# Commuta_PCBv2.net
KiCad netlist of a schematic drawn in EasyEDA Pro
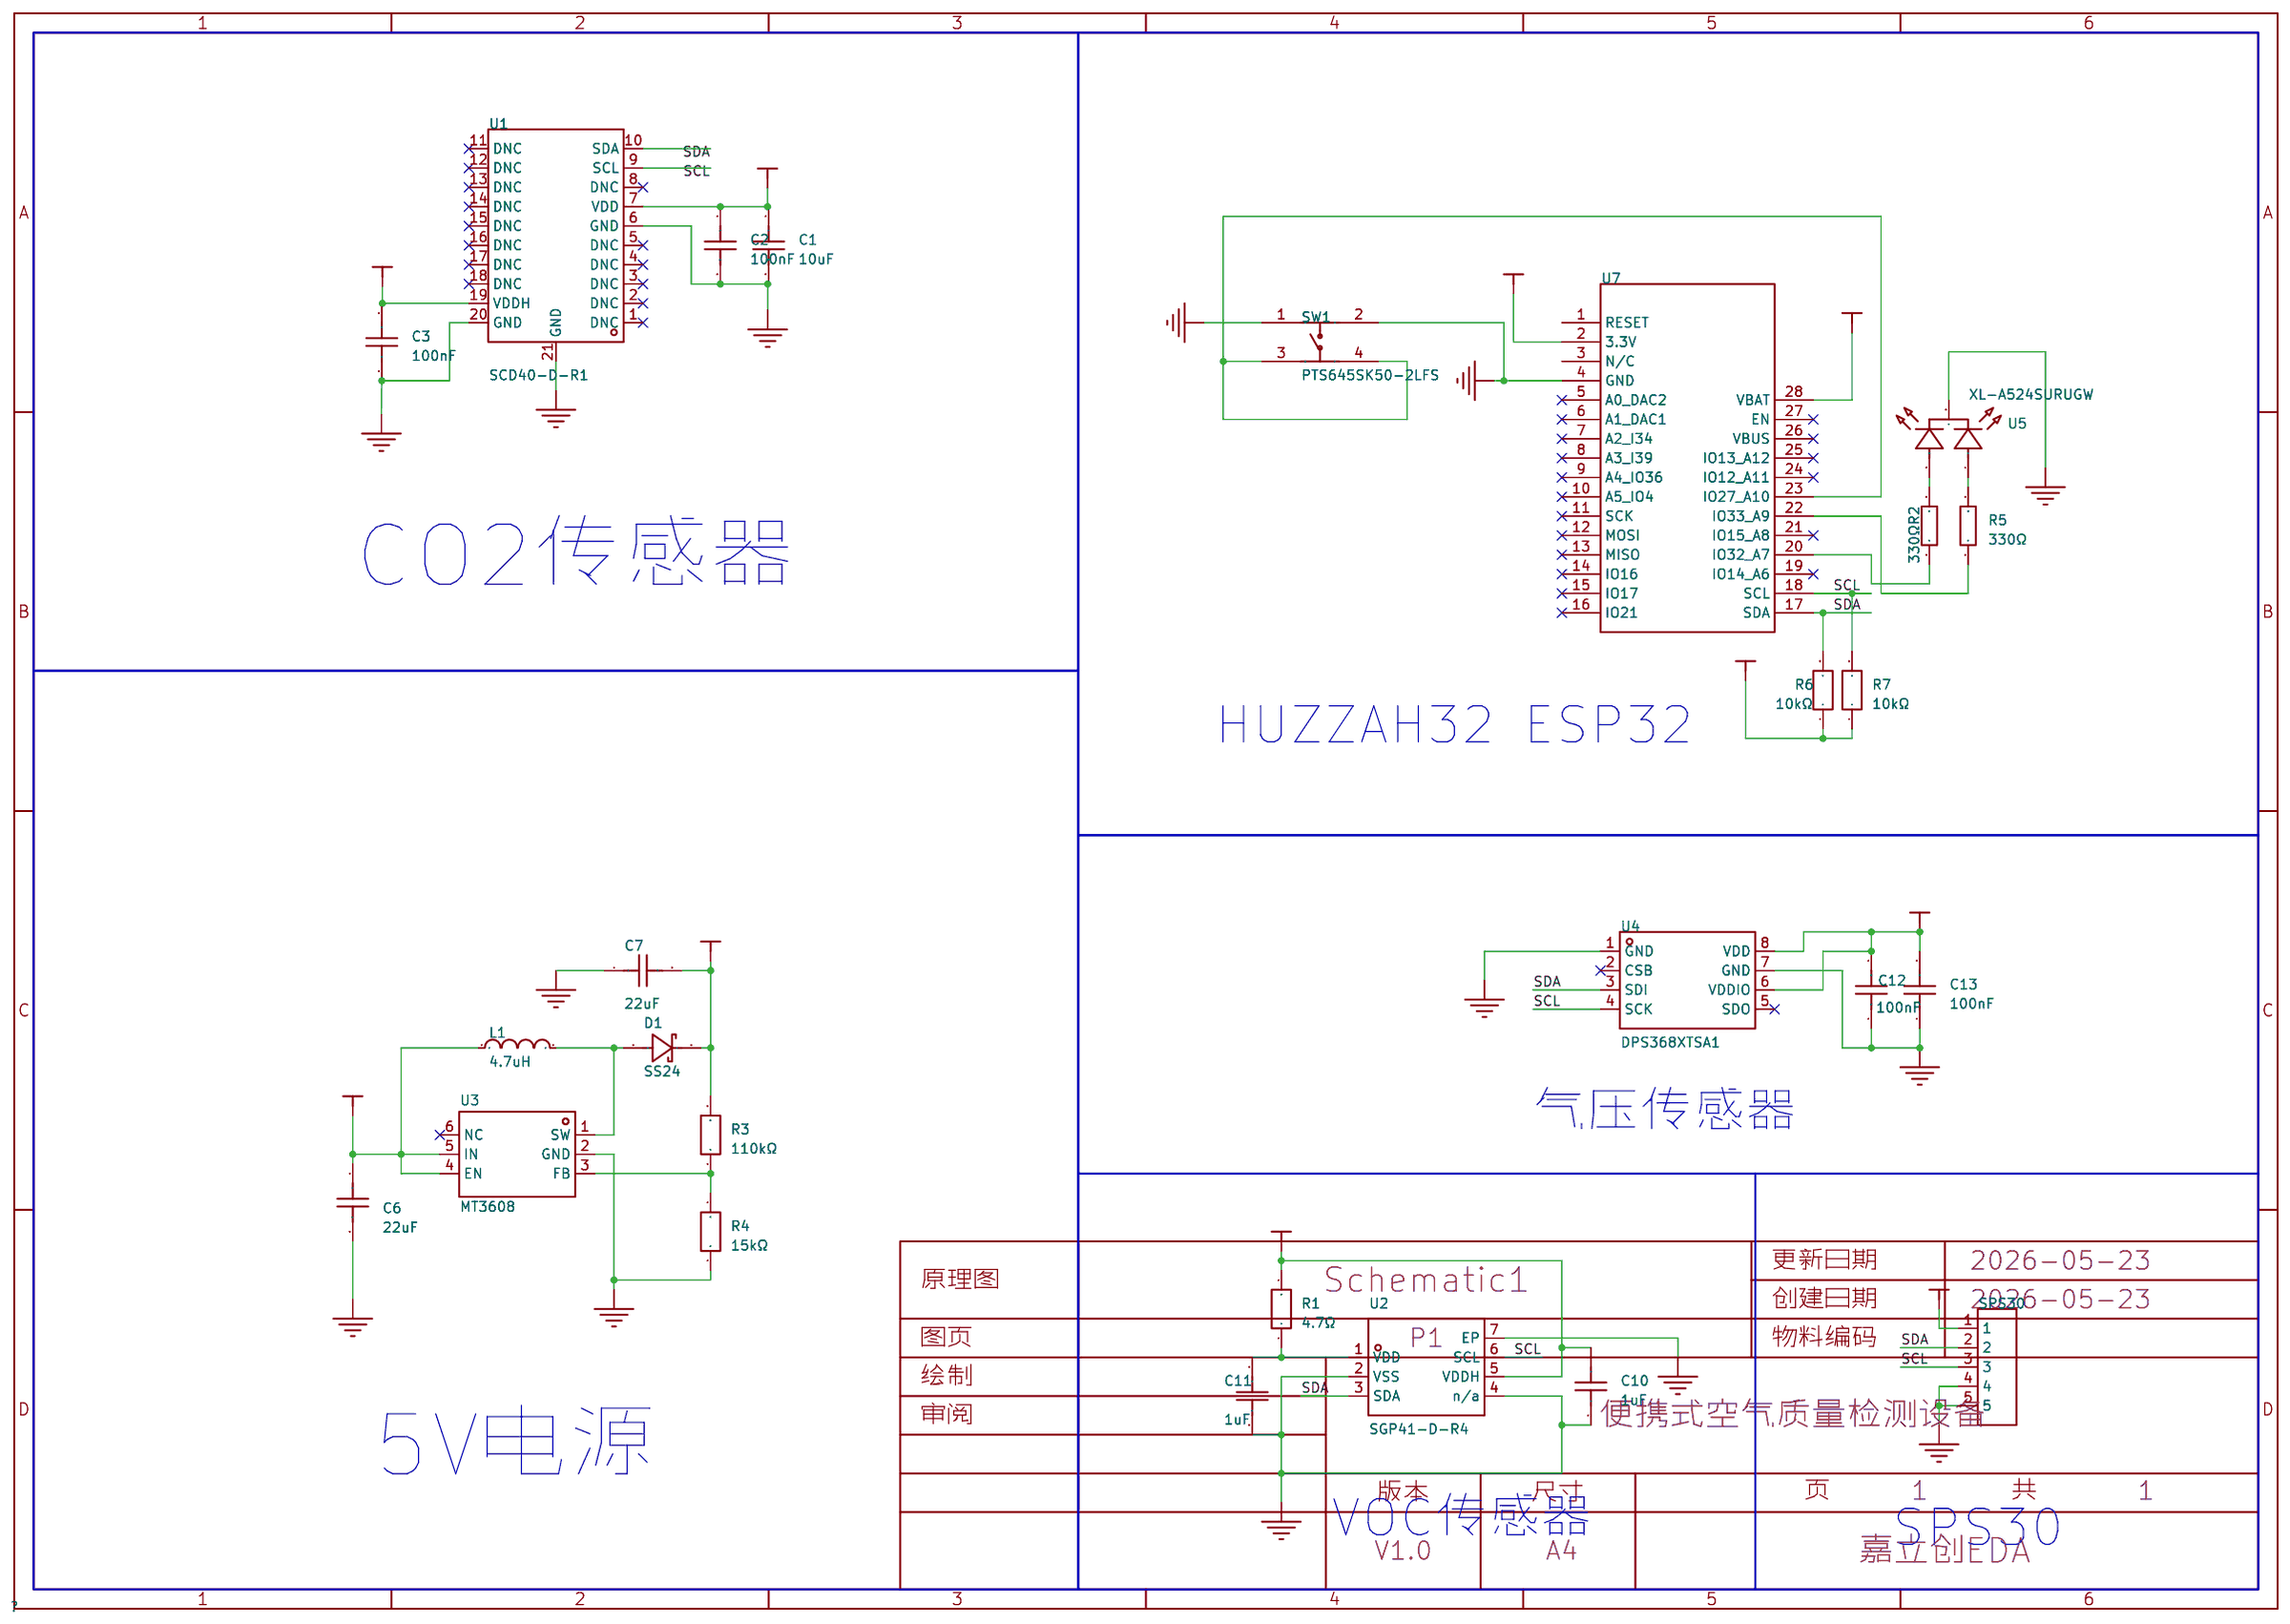
[diagram p0: schematic sheet]

(export (version "E")
  (design (tool "Eeschema 10.0.6"))
  (components
    (comp (ref "C1")
      (value "10uF")
      (footprint "easyedapro:C0805")
      (fields
        (field (name "Manufacturer Part") "CGA0805X5R106K250MT")
        (field (name "Manufacturer") "HRE(芯声)")
      )
      (libsource (lib "easyedapro") (part "CGA0805X5R106K250MT"))
    )
    (comp (ref "C2")
      (value "100nF")
      (footprint "easyedapro:C0603")
      (fields
        (field (name "Manufacturer Part") "CGA0603X7R104K500JT")
        (field (name "Manufacturer") "HRE(芯声)")
      )
      (libsource (lib "easyedapro") (part "CGA0603X7R104K500JT"))
    )
    (comp (ref "C3")
      (value "100nF")
      (footprint "easyedapro:C0603")
      (fields
        (field (name "Manufacturer Part") "CGA0603X7R104K500JT")
        (field (name "Manufacturer") "HRE(芯声)")
      )
      (libsource (lib "easyedapro") (part "CGA0603X7R104K500JT"))
    )
    (comp (ref "C6")
      (value "22uF")
      (footprint "easyedapro:C0603")
      (fields
        (field (name "Manufacturer Part") "CGA0603X5R226M160JT")
        (field (name "Manufacturer") "HRE(芯声)")
      )
      (libsource (lib "easyedapro") (part "CGA0603X5R226M160JT"))
    )
    (comp (ref "C7")
      (value "22uF")
      (footprint "easyedapro:C0603")
      (fields
        (field (name "Manufacturer Part") "CGA0603X5R226M160JT")
        (field (name "Manufacturer") "HRE(芯声)")
      )
      (libsource (lib "easyedapro") (part "CGA0603X5R226M160JT"))
    )
    (comp (ref "C10")
      (value "1uF")
      (footprint "easyedapro:C0603")
      (fields
        (field (name "Manufacturer Part") "CGA0603X5R105K500JT")
        (field (name "Manufacturer") "HRE(芯声)")
      )
      (libsource (lib "easyedapro") (part "CGA0603X5R105K500JT"))
    )
    (comp (ref "C11")
      (value "1uF")
      (footprint "easyedapro:C0603")
      (fields
        (field (name "Manufacturer Part") "CGA0603X5R105K500JT")
        (field (name "Manufacturer") "HRE(芯声)")
      )
      (libsource (lib "easyedapro") (part "CGA0603X5R105K500JT"))
    )
    (comp (ref "C12")
      (value "100nF")
      (footprint "easyedapro:C0603")
      (fields
        (field (name "Manufacturer Part") "CGA0603X7R104K500JT")
        (field (name "Manufacturer") "HRE(芯声)")
      )
      (libsource (lib "easyedapro") (part "CGA0603X7R104K500JT"))
    )
    (comp (ref "C13")
      (value "100nF")
      (footprint "easyedapro:C0603")
      (fields
        (field (name "Manufacturer Part") "CGA0603X7R104K500JT")
        (field (name "Manufacturer") "HRE(芯声)")
      )
      (libsource (lib "easyedapro") (part "CGA0603X7R104K500JT"))
    )
    (comp (ref "D1")
      (value "SS24")
      (footprint "easyedapro:SMA_L4.3-W2.6-LS5.0-FD")
      (fields (field (name "Manufacturer") "R+O(宏嘉诚)"))
      (libsource (lib "easyedapro") (part "SS24_C7420362"))
    )
    (comp (ref "L1")
      (value "4.7uH")
      (footprint "easyedapro:IND-SMD_L5.0-W5.0_FNR50XXS")
      (fields (field (name "Manufacturer Part") "FNR5040S4R7MT") (field (name "Manufacturer") "cjiang(长江微电)"))
      (libsource (lib "easyedapro") (part "FNR5040S4R7MT"))
    )
    (comp (ref "R1")
      (value "4.7Ω")
      (footprint "easyedapro:R0603")
      (fields (field (name "Manufacturer Part") "FRC0603F1001TS") (field (name "Manufacturer") "FOJAN(富捷)"))
      (libsource (lib "easyedapro") (part "FRC0603F1001TS"))
    )
    (comp (ref "R2")
      (value "330Ω")
      (footprint "easyedapro:R0603")
      (fields
        (field (name "Manufacturer Part") "0603WAF3303T5E")
        (field (name "Manufacturer") "UNI-ROYAL(厚声)")
      )
      (libsource (lib "easyedapro") (part "0603WAF3303T5E"))
    )
    (comp (ref "R3")
      (value "110kΩ")
      (footprint "easyedapro:R0603")
      (fields (field (name "Manufacturer Part") "FRC0603F1103TS") (field (name "Manufacturer") "FOJAN(富捷)"))
      (libsource (lib "easyedapro") (part "FRC0603F1103TS"))
    )
    (comp (ref "R4")
      (value "15kΩ")
      (footprint "easyedapro:R0603")
      (fields (field (name "Manufacturer Part") "FRC0603F1502TS") (field (name "Manufacturer") "FOJAN(富捷)"))
      (libsource (lib "easyedapro") (part "FRC0603F1502TS"))
    )
    (comp (ref "R5")
      (value "330Ω")
      (footprint "easyedapro:R0603")
      (fields
        (field (name "Manufacturer Part") "0603WAF3303T5E")
        (field (name "Manufacturer") "UNI-ROYAL(厚声)")
      )
      (libsource (lib "easyedapro") (part "0603WAF3303T5E"))
    )
    (comp (ref "R6")
      (value "10kΩ")
      (footprint "easyedapro:R0603")
      (fields (field (name "Manufacturer Part") "FRC0603J103 TS") (field (name "Manufacturer") "FOJAN(富捷)"))
      (libsource (lib "easyedapro") (part "FRC0603J103TS"))
    )
    (comp (ref "R7")
      (value "10kΩ")
      (footprint "easyedapro:R0603")
      (fields (field (name "Manufacturer Part") "FRC0603J103 TS") (field (name "Manufacturer") "FOJAN(富捷)"))
      (libsource (lib "easyedapro") (part "FRC0603J103TS"))
    )
    (comp (ref "SPS30")
      (value "PZ254V-11-05P")
      (footprint "easyedapro:HDR-TH_5P-P2.54-V-M")
      (fields (field (name "Manufacturer") "XFCN(兴飞)"))
      (libsource (lib "easyedapro") (part "PZ254V-11-05P"))
    )
    (comp (ref "SW1")
      (value "PTS645SK50-2LFS")
      (footprint "easyedapro:KEY-TH_4P-L6.0-W6.0-P4.50-LS6.50")
      (fields (field (name "Manufacturer") "C&K"))
      (libsource (lib "easyedapro") (part "PTS645SK50-2LFS"))
    )
    (comp (ref "U1")
      (value "SCD40-D-R1")
      (footprint "easyedapro:LGA-20_L10.1-W10.1-P1.25-TL")
      (fields (field (name "Manufacturer") "Sensirion(瑞士盛思锐)"))
      (libsource (lib "easyedapro") (part "SCD40-D-R1"))
    )
    (comp (ref "U2")
      (value "SGP41-D-R4")
      (footprint "easyedapro:DFN-6_L2.4-W2.4-P0.80-TL-EP")
      (fields (field (name "Manufacturer") "Sensirion(瑞士盛思锐)"))
      (libsource (lib "easyedapro") (part "SGP41-D-R4"))
    )
    (comp (ref "U3")
      (value "MT3608")
      (footprint "easyedapro:SOT-23-6_L2.9-W1.6-P0.95-LS2.8-BL")
      (fields (field (name "Manufacturer") "西安航天民芯"))
      (libsource (lib "easyedapro") (part "MT3608"))
    )
    (comp (ref "U4")
      (value "DPS368XTSA1")
      (footprint "easyedapro:LGA-8_L2.5-W2.0-P0.65-TR_DPS368")
      (fields (field (name "Manufacturer") "Infineon(英飞凌)"))
      (libsource (lib "easyedapro") (part "DPS368XTSA1"))
    )
    (comp (ref "U5")
      (value "XL-A524SURUGW")
      (footprint "easyedapro:LED-TH_3P-BD5.8-P2.54-1")
      (fields (field (name "Manufacturer") "XINGLIGHT(成兴光)"))
      (libsource (lib "easyedapro") (part "XL-A524SURUGW"))
    )
    (comp (ref "U7") (value "~") (libsource (lib "easyedapro") (part "HUZZAH32 ESP32")))
  )
  (nets
    (net (code "1") (name "+3.3V") (class "Default")
      (node (ref "C1") (pin "1") (pinfunction "1_1") (pintype "unspecified"))
      (node (ref "C10") (pin "2") (pinfunction "2_2") (pintype "unspecified"))
      (node (ref "C12") (pin "2") (pinfunction "2_2") (pintype "unspecified"))
      (node (ref "C13") (pin "2") (pinfunction "2_2") (pintype "unspecified"))
      (node (ref "C2") (pin "1") (pinfunction "1_1") (pintype "unspecified"))
      (node (ref "C3") (pin "1") (pinfunction "1_1") (pintype "unspecified"))
      (node (ref "R1") (pin "2") (pinfunction "2_2") (pintype "unspecified"))
      (node (ref "R6") (pin "1") (pinfunction "1_1") (pintype "unspecified"))
      (node (ref "R7") (pin "1") (pinfunction "1_1") (pintype "unspecified"))
      (node (ref "U1") (pin "19") (pinfunction "VDDH_19") (pintype "unspecified"))
      (node (ref "U1") (pin "7") (pinfunction "VDD_7") (pintype "unspecified"))
      (node (ref "U2") (pin "5") (pinfunction "VDDH_5") (pintype "unspecified"))
      (node (ref "U4") (pin "6") (pinfunction "VDDIO_6") (pintype "unspecified"))
      (node (ref "U4") (pin "8") (pinfunction "VDD_8") (pintype "unspecified"))
      (node (ref "U7") (pin "2") (pinfunction "3.3V_2") (pintype "unspecified"))
    )
    (net (code "2") (name "+5V") (class "Default")
      (node (ref "C7") (pin "2") (pinfunction "2_2") (pintype "unspecified"))
      (node (ref "D1") (pin "2") (pinfunction "K_2") (pintype "unspecified"))
      (node (ref "R3") (pin "2") (pinfunction "2_2") (pintype "unspecified"))
      (node (ref "SPS30") (pin "1") (pinfunction "1_1") (pintype "unspecified"))
    )
    (net (code "3") (name "/SCL") (class "Default")
      (node (ref "R7") (pin "2") (pinfunction "2_2") (pintype "unspecified"))
      (node (ref "SPS30") (pin "3") (pinfunction "3_3") (pintype "unspecified"))
      (node (ref "U1") (pin "9") (pinfunction "SCL_9") (pintype "unspecified"))
      (node (ref "U2") (pin "6") (pinfunction "SCL_6") (pintype "unspecified"))
      (node (ref "U4") (pin "4") (pinfunction "SCK_4") (pintype "unspecified"))
      (node (ref "U7") (pin "18") (pinfunction "SCL_18") (pintype "unspecified"))
    )
    (net (code "4") (name "/SDA") (class "Default")
      (node (ref "R6") (pin "2") (pinfunction "2_2") (pintype "unspecified"))
      (node (ref "SPS30") (pin "2") (pinfunction "2_2") (pintype "unspecified"))
      (node (ref "U1") (pin "10") (pinfunction "SDA_10") (pintype "unspecified"))
      (node (ref "U2") (pin "3") (pinfunction "SDA_3") (pintype "unspecified"))
      (node (ref "U4") (pin "3") (pinfunction "SDI_3") (pintype "unspecified"))
      (node (ref "U7") (pin "17") (pinfunction "SDA_17") (pintype "unspecified"))
    )
    (net (code "5") (name "GND") (class "Default")
      (node (ref "C1") (pin "2") (pinfunction "2_2") (pintype "unspecified"))
      (node (ref "C10") (pin "1") (pinfunction "1_1") (pintype "unspecified"))
      (node (ref "C11") (pin "2") (pinfunction "2_2") (pintype "unspecified"))
      (node (ref "C12") (pin "1") (pinfunction "1_1") (pintype "unspecified"))
      (node (ref "C13") (pin "1") (pinfunction "1_1") (pintype "unspecified"))
      (node (ref "C2") (pin "2") (pinfunction "2_2") (pintype "unspecified"))
      (node (ref "C3") (pin "2") (pinfunction "2_2") (pintype "unspecified"))
      (node (ref "C6") (pin "2") (pinfunction "2_2") (pintype "unspecified"))
      (node (ref "C7") (pin "1") (pinfunction "1_1") (pintype "unspecified"))
      (node (ref "R4") (pin "1") (pinfunction "1_1") (pintype "unspecified"))
      (node (ref "SPS30") (pin "4") (pinfunction "4_4") (pintype "unspecified"))
      (node (ref "SPS30") (pin "5") (pinfunction "5_5") (pintype "unspecified"))
      (node (ref "SW1") (pin "1") (pinfunction "1_1") (pintype "unspecified"))
      (node (ref "SW1") (pin "2") (pinfunction "2_2") (pintype "unspecified"))
      (node (ref "U1") (pin "20") (pinfunction "GND_20") (pintype "unspecified"))
      (node (ref "U1") (pin "21") (pinfunction "GND_21") (pintype "unspecified"))
      (node (ref "U1") (pin "6") (pinfunction "GND_6") (pintype "unspecified"))
      (node (ref "U2") (pin "2") (pinfunction "VSS_2") (pintype "unspecified"))
      (node (ref "U2") (pin "4") (pinfunction "n/a_4") (pintype "unspecified"))
      (node (ref "U2") (pin "7") (pinfunction "EP_7") (pintype "unspecified"))
      (node (ref "U3") (pin "2") (pinfunction "GND_2") (pintype "unspecified"))
      (node (ref "U4") (pin "1") (pinfunction "GND_1") (pintype "unspecified"))
      (node (ref "U4") (pin "7") (pinfunction "GND_7") (pintype "unspecified"))
      (node (ref "U5") (pin "2") (pinfunction "K_2") (pintype "unspecified"))
      (node (ref "U7") (pin "4") (pinfunction "GND_4") (pintype "unspecified"))
    )
    (net (code "6") (name "Net-(D1-A)") (class "Default")
      (node (ref "D1") (pin "1") (pinfunction "A_1") (pintype "unspecified"))
      (node (ref "L1") (pin "1") (pinfunction "1_1") (pintype "unspecified"))
      (node (ref "U3") (pin "1") (pinfunction "SW_1") (pintype "unspecified"))
    )
    (net (code "7") (name "Net-(R2-Pad2)") (class "Default")
      (node (ref "R2") (pin "2") (pinfunction "2_2") (pintype "input"))
      (node (ref "U5") (pin "3") (pinfunction "A_3") (pintype "unspecified"))
    )
    (net (code "8") (name "Net-(R5-Pad2)") (class "Default")
      (node (ref "R5") (pin "2") (pinfunction "2_2") (pintype "input"))
      (node (ref "U5") (pin "1") (pinfunction "A_1") (pintype "unspecified"))
    )
    (net (code "9") (name "Net-(U2-VDD)") (class "Default")
      (node (ref "C11") (pin "1") (pinfunction "1_1") (pintype "unspecified"))
      (node (ref "R1") (pin "1") (pinfunction "1_1") (pintype "unspecified"))
      (node (ref "U2") (pin "1") (pinfunction "VDD_1") (pintype "unspecified"))
    )
    (net (code "10") (name "Net-(U3-FB)") (class "Default")
      (node (ref "R3") (pin "1") (pinfunction "1_1") (pintype "unspecified"))
      (node (ref "R4") (pin "2") (pinfunction "2_2") (pintype "unspecified"))
      (node (ref "U3") (pin "3") (pinfunction "FB_3") (pintype "unspecified"))
    )
    (net (code "11") (name "Net-(U7-IO27_A10)") (class "Default")
      (node (ref "SW1") (pin "3") (pinfunction "3_3") (pintype "unspecified"))
      (node (ref "SW1") (pin "4") (pinfunction "4_4") (pintype "unspecified"))
      (node (ref "U7") (pin "23") (pinfunction "IO27_A10_23") (pintype "unspecified"))
    )
    (net (code "12") (name "Net-(U7-IO32_A7)") (class "Default")
      (node (ref "R2") (pin "1") (pinfunction "1_1") (pintype "input"))
      (node (ref "U7") (pin "20") (pinfunction "IO32_A7_20") (pintype "unspecified"))
    )
    (net (code "13") (name "Net-(U7-IO33_A9)") (class "Default")
      (node (ref "R5") (pin "1") (pinfunction "1_1") (pintype "input"))
      (node (ref "U7") (pin "22") (pinfunction "IO33_A9_22") (pintype "unspecified"))
    )
    (net (code "14") (name "VBAT") (class "Default")
      (node (ref "C6") (pin "1") (pinfunction "1_1") (pintype "unspecified"))
      (node (ref "L1") (pin "2") (pinfunction "2_2") (pintype "unspecified"))
      (node (ref "U3") (pin "4") (pinfunction "EN_4") (pintype "unspecified"))
      (node (ref "U3") (pin "5") (pinfunction "IN_5") (pintype "unspecified"))
      (node (ref "U7") (pin "28") (pinfunction "VBAT_28") (pintype "unspecified"))
    )
    (net (code "15") (name "unconnected-(U1-DNC-Pad1)") (class "Default")
      (node (ref "U1") (pin "1") (pinfunction "DNC_1") (pintype "unspecified+no_connect"))
    )
    (net (code "16") (name "unconnected-(U1-DNC-Pad2)") (class "Default")
      (node (ref "U1") (pin "2") (pinfunction "DNC_2") (pintype "unspecified+no_connect"))
    )
    (net (code "17") (name "unconnected-(U1-DNC-Pad3)") (class "Default")
      (node (ref "U1") (pin "3") (pinfunction "DNC_3") (pintype "unspecified+no_connect"))
    )
    (net (code "18") (name "unconnected-(U1-DNC-Pad4)") (class "Default")
      (node (ref "U1") (pin "4") (pinfunction "DNC_4") (pintype "unspecified+no_connect"))
    )
    (net (code "19") (name "unconnected-(U1-DNC-Pad5)") (class "Default")
      (node (ref "U1") (pin "5") (pinfunction "DNC_5") (pintype "unspecified+no_connect"))
    )
    (net (code "20") (name "unconnected-(U1-DNC-Pad8)") (class "Default")
      (node (ref "U1") (pin "8") (pinfunction "DNC_8") (pintype "unspecified+no_connect"))
    )
    (net (code "21") (name "unconnected-(U1-DNC-Pad11)") (class "Default")
      (node (ref "U1") (pin "11") (pinfunction "DNC_11") (pintype "unspecified+no_connect"))
    )
    (net (code "22") (name "unconnected-(U1-DNC-Pad12)") (class "Default")
      (node (ref "U1") (pin "12") (pinfunction "DNC_12") (pintype "unspecified+no_connect"))
    )
    (net (code "23") (name "unconnected-(U1-DNC-Pad13)") (class "Default")
      (node (ref "U1") (pin "13") (pinfunction "DNC_13") (pintype "unspecified+no_connect"))
    )
    (net (code "24") (name "unconnected-(U1-DNC-Pad14)") (class "Default")
      (node (ref "U1") (pin "14") (pinfunction "DNC_14") (pintype "unspecified+no_connect"))
    )
    (net (code "25") (name "unconnected-(U1-DNC-Pad15)") (class "Default")
      (node (ref "U1") (pin "15") (pinfunction "DNC_15") (pintype "unspecified+no_connect"))
    )
    (net (code "26") (name "unconnected-(U1-DNC-Pad16)") (class "Default")
      (node (ref "U1") (pin "16") (pinfunction "DNC_16") (pintype "unspecified+no_connect"))
    )
    (net (code "27") (name "unconnected-(U1-DNC-Pad17)") (class "Default")
      (node (ref "U1") (pin "17") (pinfunction "DNC_17") (pintype "unspecified+no_connect"))
    )
    (net (code "28") (name "unconnected-(U1-DNC-Pad18)") (class "Default")
      (node (ref "U1") (pin "18") (pinfunction "DNC_18") (pintype "unspecified+no_connect"))
    )
    (net (code "29") (name "unconnected-(U3-NC-Pad6)") (class "Default")
      (node (ref "U3") (pin "6") (pinfunction "NC_6") (pintype "unspecified+no_connect"))
    )
    (net (code "30") (name "unconnected-(U4-CSB-Pad2)") (class "Default")
      (node (ref "U4") (pin "2") (pinfunction "CSB_2") (pintype "unspecified+no_connect"))
    )
    (net (code "31") (name "unconnected-(U4-SDO-Pad5)") (class "Default")
      (node (ref "U4") (pin "5") (pinfunction "SDO_5") (pintype "unspecified+no_connect"))
    )
    (net (code "32") (name "unconnected-(U7-A0_DAC2-Pad5)") (class "Default")
      (node (ref "U7") (pin "5") (pinfunction "A0_DAC2_5") (pintype "unspecified+no_connect"))
    )
    (net (code "33") (name "unconnected-(U7-A1_DAC1-Pad6)") (class "Default")
      (node (ref "U7") (pin "6") (pinfunction "A1_DAC1_6") (pintype "unspecified+no_connect"))
    )
    (net (code "34") (name "unconnected-(U7-A2_I34-Pad7)") (class "Default")
      (node (ref "U7") (pin "7") (pinfunction "A2_I34_7") (pintype "unspecified+no_connect"))
    )
    (net (code "35") (name "unconnected-(U7-A3_I39-Pad8)") (class "Default")
      (node (ref "U7") (pin "8") (pinfunction "A3_I39_8") (pintype "unspecified+no_connect"))
    )
    (net (code "36") (name "unconnected-(U7-A4_IO36-Pad9)") (class "Default")
      (node (ref "U7") (pin "9") (pinfunction "A4_IO36_9") (pintype "unspecified+no_connect"))
    )
    (net (code "37") (name "unconnected-(U7-A5_IO4-Pad10)") (class "Default")
      (node (ref "U7") (pin "10") (pinfunction "A5_IO4_10") (pintype "unspecified+no_connect"))
    )
    (net (code "38") (name "unconnected-(U7-EN-Pad27)") (class "Default")
      (node (ref "U7") (pin "27") (pinfunction "EN_27") (pintype "unspecified+no_connect"))
    )
    (net (code "39") (name "unconnected-(U7-IO12_A11-Pad24)") (class "Default")
      (node (ref "U7") (pin "24") (pinfunction "IO12_A11_24") (pintype "unspecified+no_connect"))
    )
    (net (code "40") (name "unconnected-(U7-IO13_A12-Pad25)") (class "Default")
      (node (ref "U7") (pin "25") (pinfunction "IO13_A12_25") (pintype "unspecified+no_connect"))
    )
    (net (code "41") (name "unconnected-(U7-IO14_A6-Pad19)") (class "Default")
      (node (ref "U7") (pin "19") (pinfunction "IO14_A6_19") (pintype "unspecified+no_connect"))
    )
    (net (code "42") (name "unconnected-(U7-IO15_A8-Pad21)") (class "Default")
      (node (ref "U7") (pin "21") (pinfunction "IO15_A8_21") (pintype "unspecified+no_connect"))
    )
    (net (code "43") (name "unconnected-(U7-IO16-Pad14)") (class "Default")
      (node (ref "U7") (pin "14") (pinfunction "IO16_14") (pintype "unspecified+no_connect"))
    )
    (net (code "44") (name "unconnected-(U7-IO17-Pad15)") (class "Default")
      (node (ref "U7") (pin "15") (pinfunction "IO17_15") (pintype "unspecified+no_connect"))
    )
    (net (code "45") (name "unconnected-(U7-IO21-Pad16)") (class "Default")
      (node (ref "U7") (pin "16") (pinfunction "IO21_16") (pintype "unspecified+no_connect"))
    )
    (net (code "46") (name "unconnected-(U7-MISO-Pad13)") (class "Default")
      (node (ref "U7") (pin "13") (pinfunction "MISO_13") (pintype "unspecified+no_connect"))
    )
    (net (code "47") (name "unconnected-(U7-MOSI-Pad12)") (class "Default")
      (node (ref "U7") (pin "12") (pinfunction "MOSI_12") (pintype "unspecified+no_connect"))
    )
    (net (code "48") (name "unconnected-(U7-N{slash}C-Pad3)") (class "Default")
      (node (ref "U7") (pin "3") (pinfunction "N/C_3") (pintype "unspecified"))
    )
    (net (code "49") (name "unconnected-(U7-RESET-Pad1)") (class "Default")
      (node (ref "U7") (pin "1") (pinfunction "RESET_1") (pintype "unspecified"))
    )
    (net (code "50") (name "unconnected-(U7-SCK-Pad11)") (class "Default")
      (node (ref "U7") (pin "11") (pinfunction "SCK_11") (pintype "unspecified+no_connect"))
    )
    (net (code "51") (name "unconnected-(U7-VBUS-Pad26)") (class "Default")
      (node (ref "U7") (pin "26") (pinfunction "VBUS_26") (pintype "unspecified+no_connect"))
    )
  )
)
